# 20190105_ORIGAMI_V1-V-3.net
KiCad netlist of a schematic drawn in EAGLE
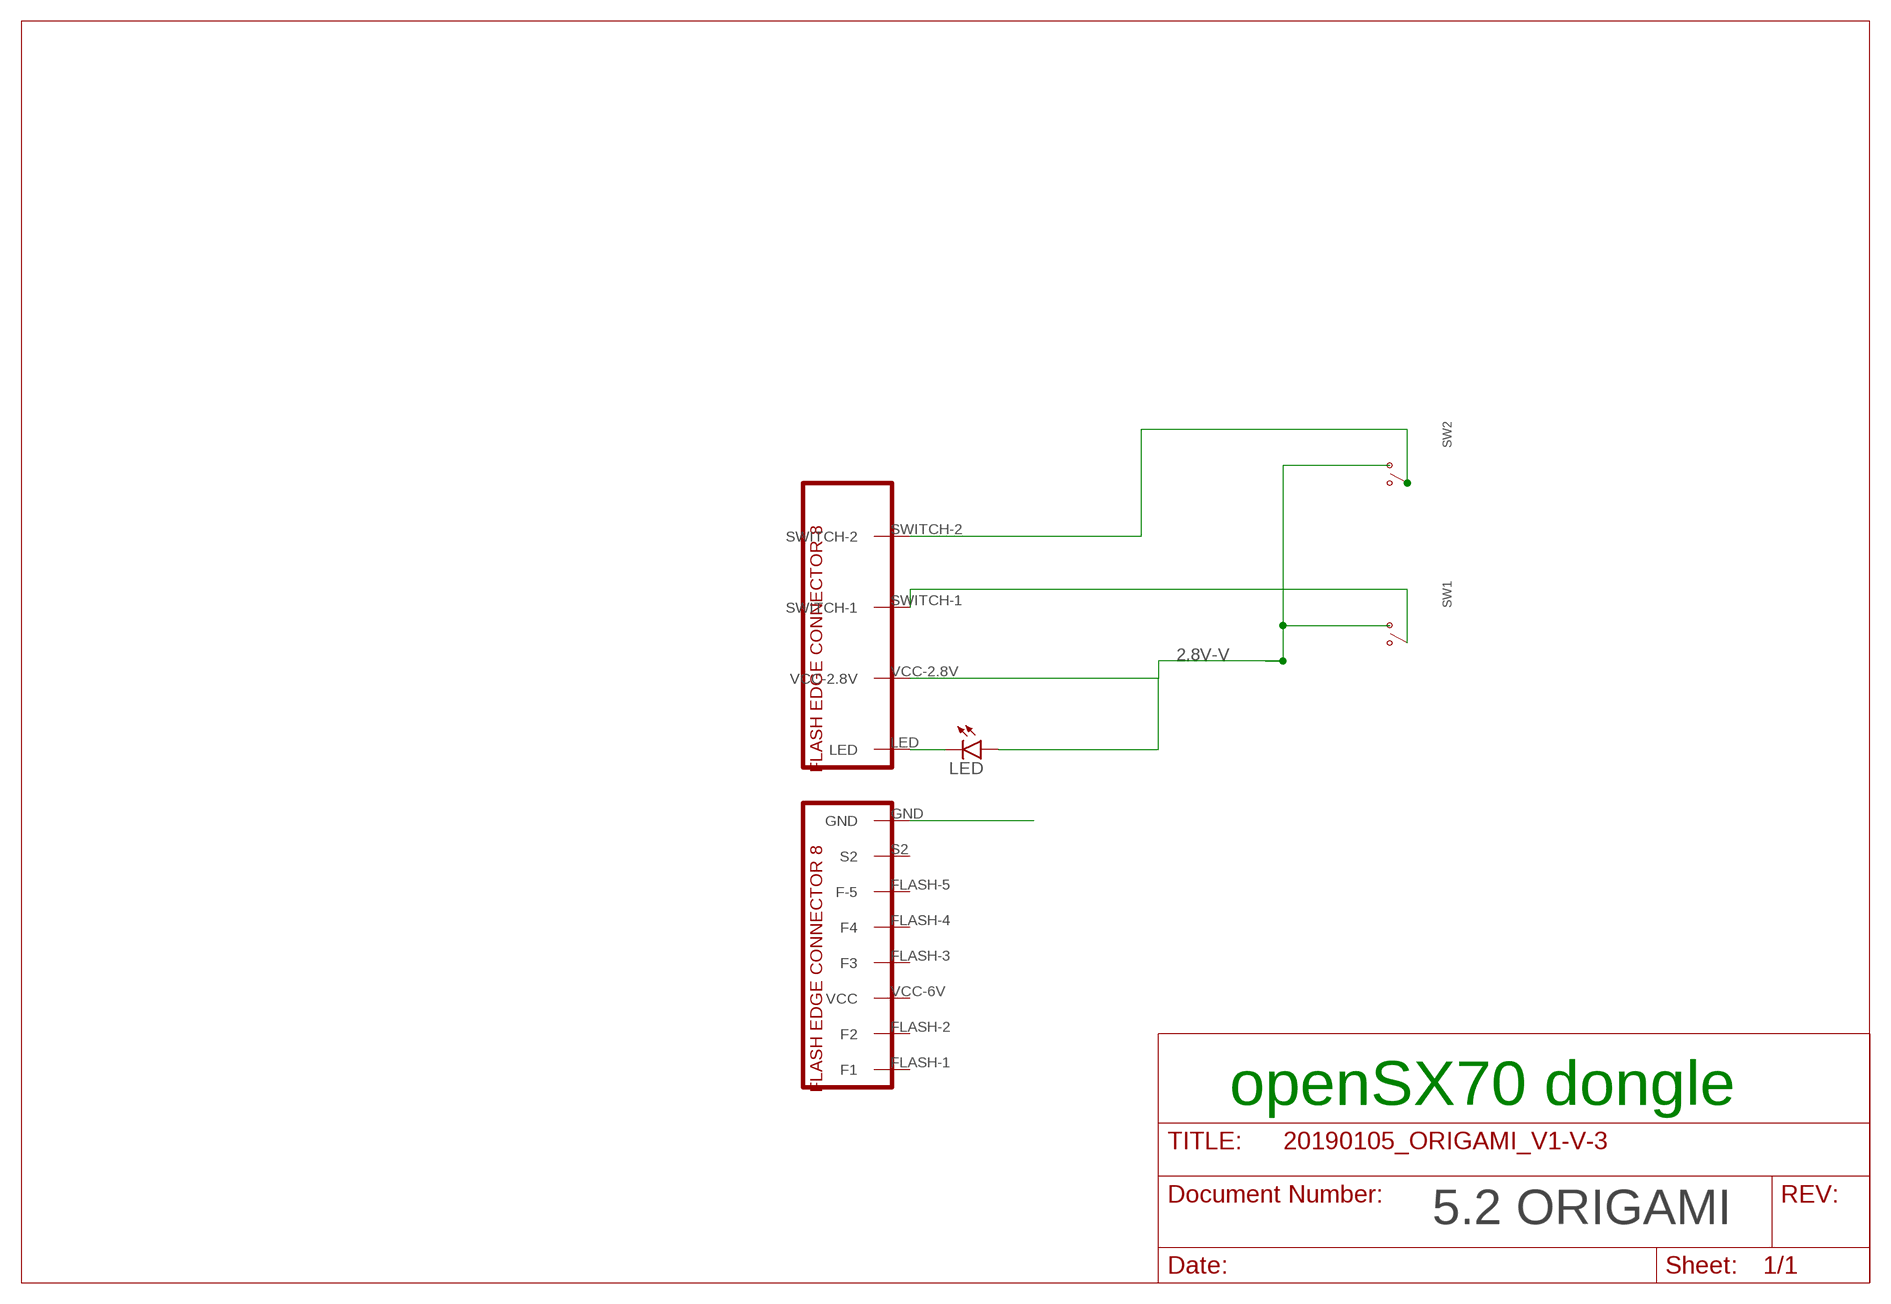
[diagram p0: schematic, sheet 1]

(export (version "E")
  (design (tool "Eeschema 10.0.6"))
  (components
    (comp (ref "LED")
      (value "LEDCHIP-LED0805")
      (footprint "eagle-import:CHIP-LED0805")
      (libsource (lib "eagle-import") (part "LEDCHIP-LED0805"))
    )
    (comp (ref "SW1")
      (value "MK-12C02 G1.5")
      (footprint "eagle-import:K3-1280S-SMALL")
      (libsource (lib "eagle-import") (part "K3-1280S-SHORTSMALL"))
    )
    (comp (ref "SW2")
      (value "MK-12C02 G1.5")
      (footprint "eagle-import:K3-1280S-SMALL")
      (libsource (lib "eagle-import") (part "K3-1280S-SHORTSMALL"))
    )
    (comp (ref "U$1")
      (value "FLASH-BRIDGE-SW1-SW2-LED-SMALL-NO-GND")
      (footprint "eagle-import:FLASH-8-BRIDGE-SW1-SW2-LED-SMALL-NO-GND")
      (libsource (lib "eagle-import") (part "FLASH-BRIDGE-SW1-SW2-LED-SMALL-NO-GND"))
    )
    (comp (ref "U$2")
      (value "SX70-FLASH-EDGE8-MALE-LONG")
      (footprint "eagle-import:SX70-FLASH-EDGE8-2")
      (libsource (lib "eagle-import") (part "SX70-FLASH-EDGE8-MALE-LONG"))
    )
  )
  (nets
    (net (code "1") (name "/2.8V-V") (class "Default")
      (node (ref "LED") (pin "A") (pinfunction "A_A") (pintype "passive"))
      (node (ref "SW1") (pin "P$3") (pinfunction "B_P$3") (pintype "bidirectional"))
      (node (ref "SW2") (pin "P$3") (pinfunction "B_P$3") (pintype "bidirectional"))
      (node (ref "U$1") (pin "VCC-2.8V") (pinfunction "VCC-2.8V_VCC-2.8V") (pintype "bidirectional"))
    )
    (net (code "2") (name "Net-(LED-PadC)") (class "Default")
      (node (ref "LED") (pin "C") (pinfunction "C_C") (pintype "passive"))
      (node (ref "U$1") (pin "LED") (pinfunction "LED_LED") (pintype "bidirectional"))
    )
    (net (code "3") (name "Net-(SW1-COM)") (class "Default")
      (node (ref "SW1") (pin "P$2") (pinfunction "COM_P$2") (pintype "bidirectional"))
      (node (ref "U$1") (pin "SWITCH-1") (pinfunction "SWITCH-1_SWITCH-1") (pintype "bidirectional"))
    )
    (net (code "4") (name "Net-(SW2-COM)") (class "Default")
      (node (ref "SW2") (pin "P$2") (pinfunction "COM_P$2") (pintype "bidirectional"))
      (node (ref "U$1") (pin "SWITCH-2") (pinfunction "SWITCH-2_SWITCH-2") (pintype "bidirectional"))
    )
    (net (code "5") (name "unconnected-(SW1-A-PadP$1)") (class "Default")
      (node (ref "SW1") (pin "P$1") (pinfunction "A_P$1") (pintype "bidirectional"))
    )
    (net (code "6") (name "unconnected-(SW2-A-PadP$1)") (class "Default")
      (node (ref "SW2") (pin "P$1") (pinfunction "A_P$1") (pintype "bidirectional"))
    )
    (net (code "7") (name "unconnected-(U$2-F-5-PadFLASH-5)") (class "Default")
      (node (ref "U$2") (pin "FLASH-5") (pinfunction "F-5_FLASH-5") (pintype "bidirectional"))
    )
    (net (code "8") (name "unconnected-(U$2-F1-PadFLASH-1)") (class "Default")
      (node (ref "U$2") (pin "FLASH-1") (pinfunction "F1_FLASH-1") (pintype "bidirectional"))
    )
    (net (code "9") (name "unconnected-(U$2-F2-PadFLASH-2)") (class "Default")
      (node (ref "U$2") (pin "FLASH-2") (pinfunction "F2_FLASH-2") (pintype "bidirectional"))
    )
    (net (code "10") (name "unconnected-(U$2-F3-PadFLASH-3)") (class "Default")
      (node (ref "U$2") (pin "FLASH-3") (pinfunction "F3_FLASH-3") (pintype "bidirectional"))
    )
    (net (code "11") (name "unconnected-(U$2-F4-PadFLASH-4)") (class "Default")
      (node (ref "U$2") (pin "FLASH-4") (pinfunction "F4_FLASH-4") (pintype "bidirectional"))
    )
    (net (code "12") (name "unconnected-(U$2-PadGND)") (class "Default")
      (node (ref "U$2") (pin "GND") (pinfunction "GND_GND") (pintype "bidirectional"))
    )
    (net (code "13") (name "unconnected-(U$2-PadS2)") (class "Default")
      (node (ref "U$2") (pin "S2") (pinfunction "S2_S2") (pintype "bidirectional"))
    )
    (net (code "14") (name "unconnected-(U$2-VCC-PadVCC-6V)") (class "Default")
      (node (ref "U$2") (pin "VCC-6V") (pinfunction "VCC_VCC-6V") (pintype "bidirectional"))
    )
  )
)
